# main.net
KiCad netlist of a schematic drawn in Altium Designer
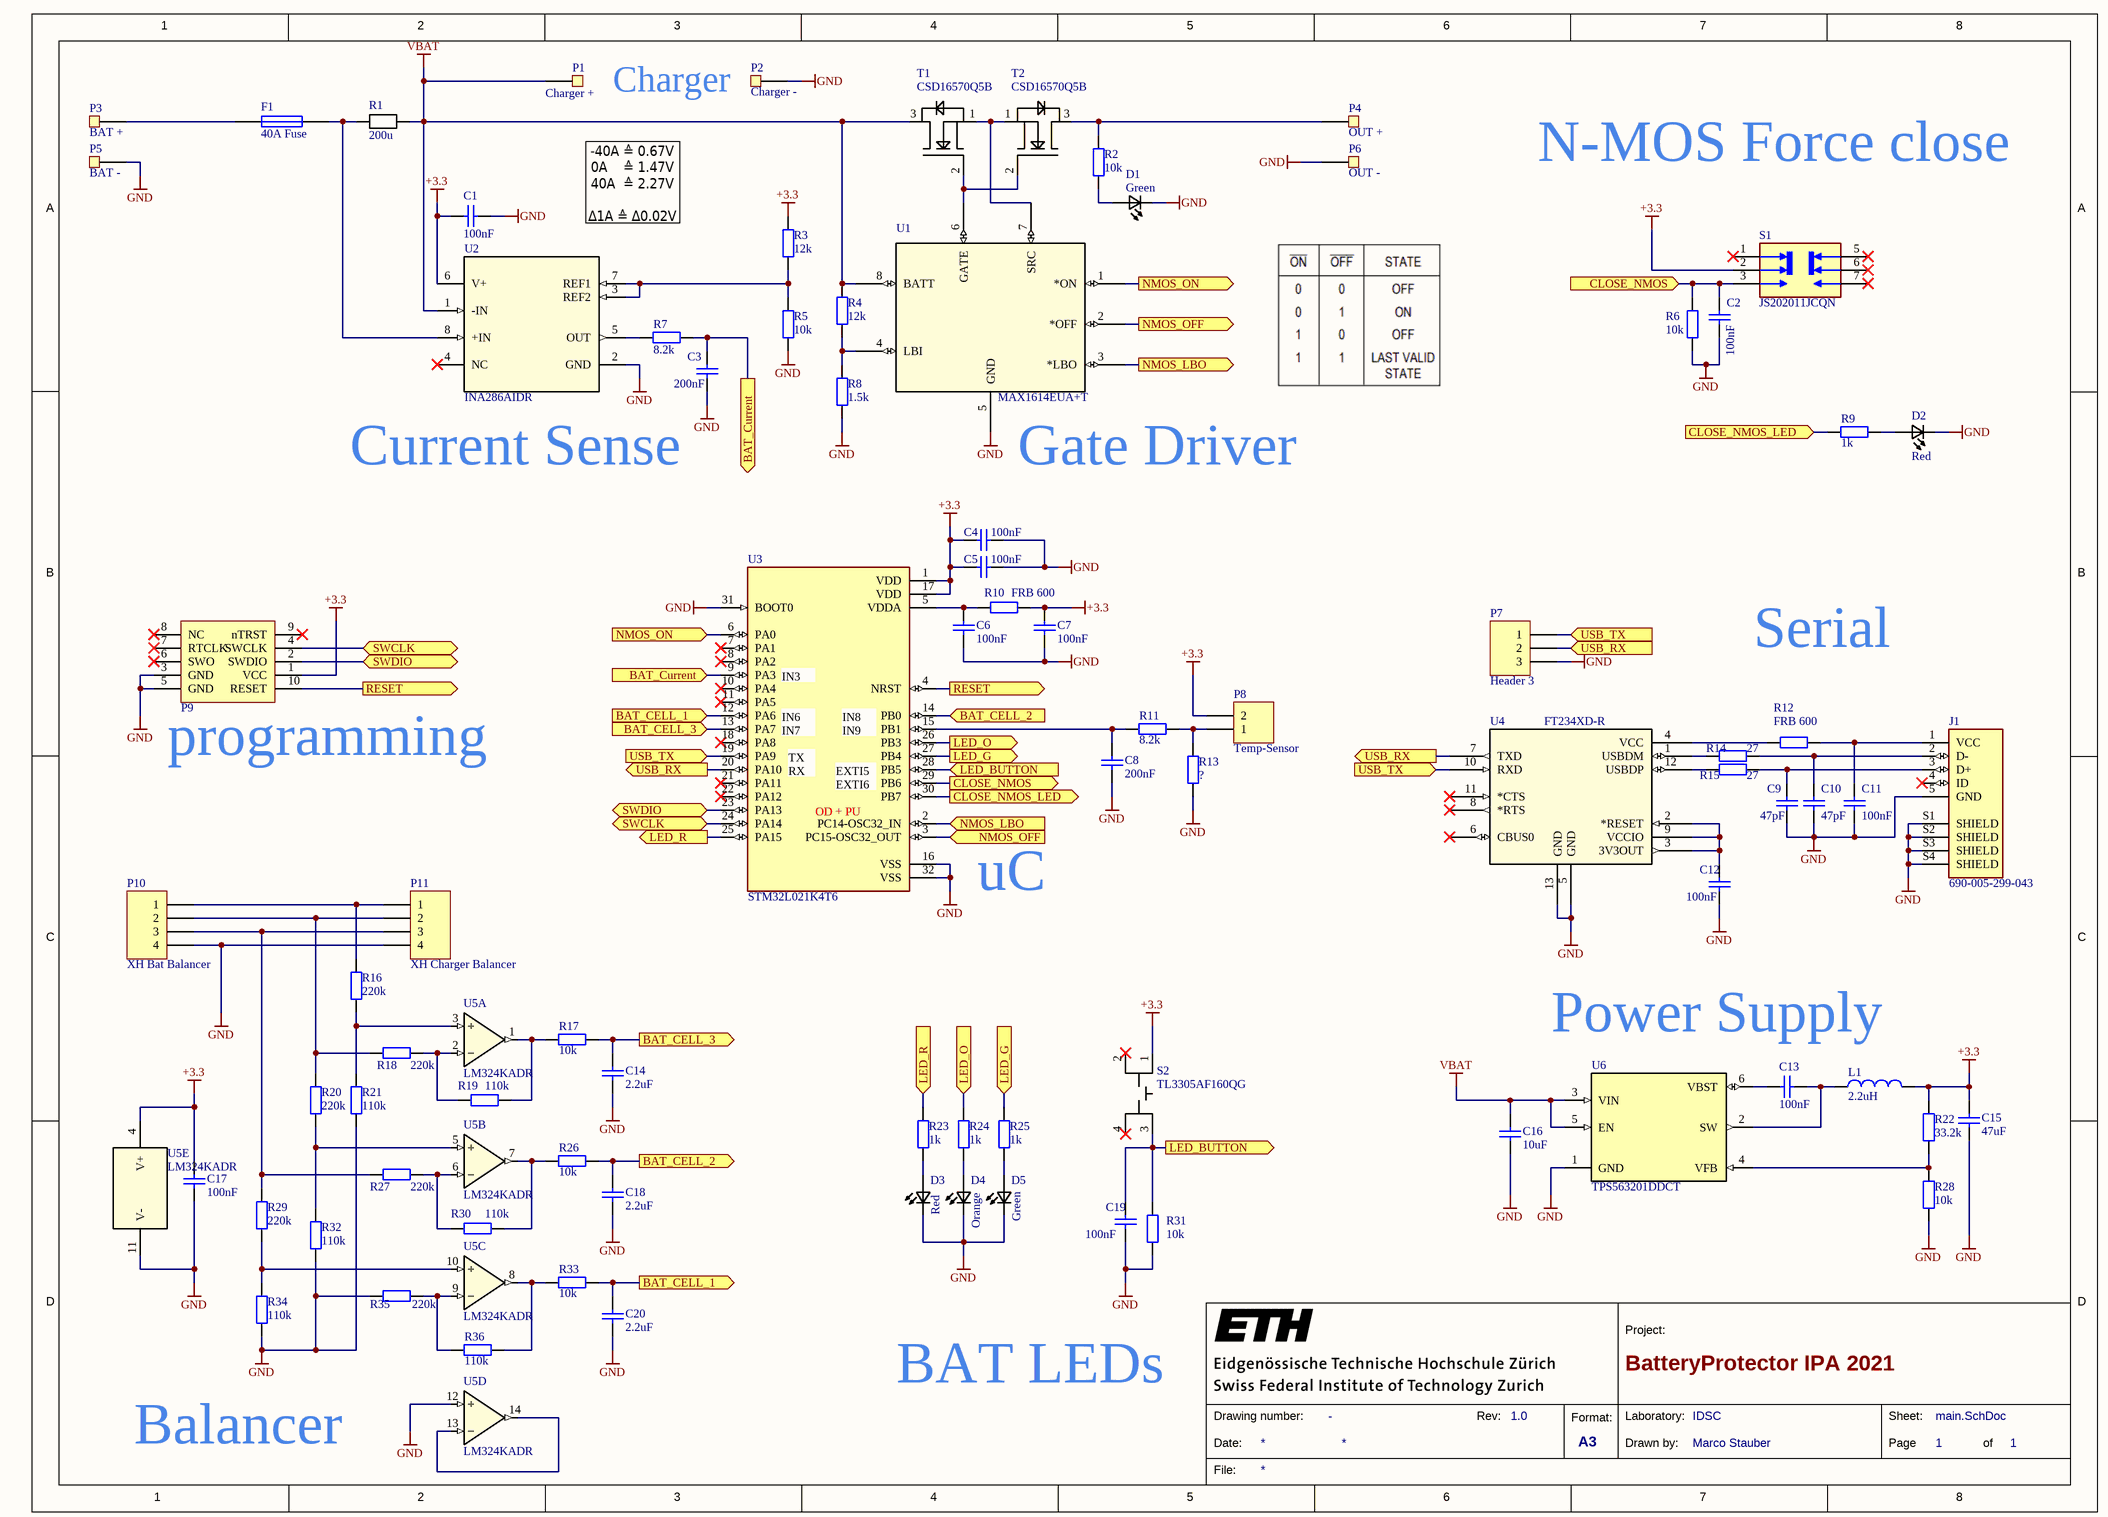
[diagram p0: main.SchDoc]

(export (version "E")
  (design (tool "Eeschema 10.0.6"))
  (components
    (comp (ref "C1")
      (value "100nF")
      (footprint "CAP_0402i_1005m -L")
      (description "capacitor")
      (libsource (lib "IDSC std generic parts") (part "Cap"))
    )
    (comp (ref "C2")
      (value "100nF")
      (footprint "CAP_0402i_1005m -L")
      (description "capacitor")
      (libsource (lib "IDSC std generic parts") (part "Cap"))
    )
    (comp (ref "C3")
      (value "200nF")
      (footprint "CAP_0402i_1005m -L")
      (description "capacitor")
      (libsource (lib "IDSC std generic parts") (part "Cap"))
    )
    (comp (ref "C4")
      (value "100nF")
      (footprint "CAP_0402i_1005m -L")
      (description "capacitor")
      (libsource (lib "IDSC std generic parts") (part "Cap"))
    )
    (comp (ref "C5")
      (value "100nF")
      (footprint "CAP_0402i_1005m -L")
      (description "capacitor")
      (libsource (lib "IDSC std generic parts") (part "Cap"))
    )
    (comp (ref "C6")
      (value "100nF")
      (footprint "CAP_0402i_1005m -L")
      (description "capacitor")
      (libsource (lib "IDSC std generic parts") (part "Cap"))
    )
    (comp (ref "C7")
      (value "100nF")
      (footprint "CAP_0402i_1005m -L")
      (description "capacitor")
      (libsource (lib "IDSC std generic parts") (part "Cap"))
    )
    (comp (ref "C8")
      (value "200nF")
      (footprint "CAP_0402i_1005m -L")
      (description "capacitor")
      (libsource (lib "IDSC std generic parts") (part "Cap"))
    )
    (comp (ref "C9")
      (value "47pF")
      (footprint "CAP_0402i_1005m -L")
      (description "capacitor")
      (libsource (lib "IDSC std generic parts") (part "Cap"))
    )
    (comp (ref "C10")
      (value "47pF")
      (footprint "CAP_0402i_1005m -L")
      (description "capacitor")
      (libsource (lib "IDSC std generic parts") (part "Cap"))
    )
    (comp (ref "C11")
      (value "100nF")
      (footprint "CAP_0402i_1005m -L")
      (description "capacitor")
      (libsource (lib "IDSC std generic parts") (part "Cap"))
    )
    (comp (ref "C12")
      (value "100nF")
      (footprint "CAP_0402i_1005m -L")
      (description "capacitor")
      (libsource (lib "IDSC std generic parts") (part "Cap"))
    )
    (comp (ref "C13")
      (value "100nF")
      (footprint "CAP_0402i_1005m -L")
      (description "capacitor")
      (libsource (lib "IDSC std generic parts") (part "Cap"))
    )
    (comp (ref "C14")
      (value "2.2uF")
      (footprint "CAP_0805i_2012m -L")
      (description "capacitor")
      (libsource (lib "IDSC std generic parts") (part "Cap"))
    )
    (comp (ref "C15")
      (value "47uF")
      (footprint "CAP_1206i_3216m -n")
      (description "capacitor")
      (libsource (lib "IDSC std generic parts") (part "Cap"))
    )
    (comp (ref "C16")
      (value "10uF")
      (footprint "CAP_0805i_2012m -L")
      (description "capacitor")
      (libsource (lib "IDSC std generic parts") (part "Cap"))
    )
    (comp (ref "C17")
      (value "100nF")
      (footprint "CAP_0402i_1005m -L")
      (description "capacitor")
      (libsource (lib "IDSC std generic parts") (part "Cap"))
    )
    (comp (ref "C18")
      (value "2.2uF")
      (footprint "CAP_0805i_2012m -L")
      (description "capacitor")
      (libsource (lib "IDSC std generic parts") (part "Cap"))
    )
    (comp (ref "C19")
      (value "100nF")
      (footprint "CAP_0402i_1005m -L")
      (description "capacitor")
      (libsource (lib "IDSC std generic parts") (part "Cap"))
    )
    (comp (ref "C20")
      (value "2.2uF")
      (footprint "CAP_0805i_2012m -L")
      (description "capacitor")
      (libsource (lib "IDSC std generic parts") (part "Cap"))
    )
    (comp (ref "D1")
      (value "Green")
      (footprint "0603_LED")
      (description "Red 631nm LED Indication - Discrete 2V 0603 _1608 Metric_")
      (fields (field (name "MF") "Lite-On Inc.") (field (name "DIGI-KEY_PART_NUMBER") "160-1447-1-ND"))
      (libsource (lib "BatteryProtector_LIB") (part "LTST-C191KRKT"))
    )
    (comp (ref "D2")
      (value "Red")
      (footprint "0603_LED")
      (description "Red 631nm LED Indication - Discrete 2V 0603 _1608 Metric_")
      (fields (field (name "MF") "Lite-On Inc.") (field (name "DIGI-KEY_PART_NUMBER") "160-1447-1-ND"))
      (libsource (lib "BatteryProtector_LIB") (part "LTST-C191KRKT"))
    )
    (comp (ref "D3")
      (value "Red")
      (footprint "0603_LED")
      (description "Red 631nm LED Indication - Discrete 2V 0603 _1608 Metric_")
      (fields (field (name "MF") "Lite-On Inc.") (field (name "DIGI-KEY_PART_NUMBER") "160-1447-1-ND"))
      (libsource (lib "BatteryProtector_LIB") (part "LTST-C191KRKT"))
    )
    (comp (ref "D4")
      (value "Orange")
      (footprint "0603_LED")
      (description "Red 631nm LED Indication - Discrete 2V 0603 _1608 Metric_")
      (fields (field (name "MF") "Lite-On Inc.") (field (name "DIGI-KEY_PART_NUMBER") "160-1447-1-ND"))
      (libsource (lib "BatteryProtector_LIB") (part "LTST-C191KRKT"))
    )
    (comp (ref "D5")
      (value "Green")
      (footprint "0603_LED")
      (description "Red 631nm LED Indication - Discrete 2V 0603 _1608 Metric_")
      (fields (field (name "MF") "Lite-On Inc.") (field (name "DIGI-KEY_PART_NUMBER") "160-1447-1-ND"))
      (libsource (lib "BatteryProtector_LIB") (part "LTST-C191KRKT"))
    )
    (comp (ref "F1")
      (value "40A Fuse")
      (footprint "FUSE_1206I_3216M_N")
      (description "Fuse")
      (libsource (lib "IDSC std generic parts") (part "Fuse"))
    )
    (comp (ref "J1")
      (value "690-005-299-043")
      (footprint "EDAC_690-005-299-043")
      (description "USB - mini B USB 2.0 Receptacle Connector 5 Position Surface Mount, Right Angle")
      (fields (field (name "MF") "EDAC Inc."))
      (libsource (lib "BatteryProtector_LIB") (part "690-005-299-043"))
    )
    (comp (ref "L1")
      (value "2.2uH")
      (footprint "IND_1210i_3225m -L")
      (description "Inductor")
      (libsource (lib "IDSC std generic parts") (part "Inductor"))
    )
    (comp (ref "P1")
      (value "Charger +")
      (footprint "AWG-10-Hole-1")
      (libsource (lib "BatteryProtector_LIB") (part "Pin"))
    )
    (comp (ref "P2") (value "Charger -") (footprint "AWG-10-Hole-1") (libsource (lib "") (part "Pin_2")))
    (comp (ref "P3") (value "BAT +") (footprint "AWG-10-Hole-1") (libsource (lib "") (part "Pin_1")))
    (comp (ref "P4")
      (value "OUT +")
      (footprint "AWG-10-Hole-1")
      (libsource (lib "BatteryProtector_LIB") (part "Pin"))
    )
    (comp (ref "P5") (value "BAT -") (footprint "AWG-10-Hole-1") (libsource (lib "") (part "Pin_1")))
    (comp (ref "P6")
      (value "OUT -")
      (footprint "AWG-10-Hole-1")
      (libsource (lib "BatteryProtector_LIB") (part "Pin"))
    )
    (comp (ref "P7")
      (value "Header 3")
      (footprint "1.27mm HDR1X3")
      (description "Header, 3-Pin")
      (libsource (lib "IDSC std connectors") (part "Header 3"))
    )
    (comp (ref "P8")
      (value "Temp-Sensor")
      (footprint "HDR1X2")
      (description "Header, 2-Pin")
      (libsource (lib "IDSC std connectors") (part "Header 2"))
    )
    (comp (ref "P9")
      (value "Tag-Connect TC2050-IDC-NL-No pin assigned")
      (footprint "TAG-CONNECT TC2050-IDC-NL 10-Pin")
      (description "10-pin pogo pin programing port")
      (libsource (lib "IDSC std connectors") (part "Tag-Connect TC2050-IDC-NL-No pin assigned"))
    )
    (comp (ref "P10")
      (value "XH Bat Balancer")
      (footprint "JST_B4B-XH-A(LF)(SN)")
      (description "Header, 4-Pin")
      (libsource (lib "BatteryProtector_LIB") (part "Header 4"))
    )
    (comp (ref "P11")
      (value "XH Charger Balancer")
      (footprint "JST_B4B-XH-A(LF)(SN)")
      (description "Header, 4-Pin")
      (libsource (lib "") (part "Header 4_1"))
    )
    (comp (ref "R1")
      (value "200u")
      (footprint "WSL3921L2000FEA")
      (description "RES 200 UOHM 1% 3W")
      (libsource (lib "BatteryProtector_LIB") (part "WSL3921L2000FEA"))
    )
    (comp (ref "R2")
      (value "10k")
      (footprint "RES_0402i_1005m -N")
      (description "Resistor")
      (libsource (lib "") (part "Res_2"))
    )
    (comp (ref "R3")
      (value "12k")
      (footprint "RES_0402i_1005m -N")
      (description "Resistor")
      (libsource (lib "") (part "Res_2"))
    )
    (comp (ref "R4")
      (value "12k")
      (footprint "RES_0402i_1005m -N")
      (description "Resistor")
      (libsource (lib "") (part "Res_2"))
    )
    (comp (ref "R5")
      (value "10k")
      (footprint "RES_0402i_1005m -N")
      (description "Resistor")
      (libsource (lib "") (part "Res_1"))
    )
    (comp (ref "R6")
      (value "10k")
      (footprint "RES_0402i_1005m -N")
      (description "Resistor")
      (libsource (lib "") (part "Res_1"))
    )
    (comp (ref "R7")
      (value "8.2k")
      (footprint "RES_0402m_1005i -L")
      (description "Resistor")
      (libsource (lib "IDSC std generic parts") (part "Res"))
    )
    (comp (ref "R8")
      (value "1.5k")
      (footprint "RES_0402i_1005m -N")
      (description "Resistor")
      (libsource (lib "") (part "Res_1"))
    )
    (comp (ref "R9")
      (value "1k")
      (footprint "RES_0402i_1005m -N")
      (description "Resistor")
      (libsource (lib "") (part "Res_3"))
    )
    (comp (ref "R10")
      (value "FRB 600")
      (footprint "RES_0603i_1608m -N")
      (description "Resistor")
      (libsource (lib "IDSC std generic parts") (part "Res"))
    )
    (comp (ref "R11")
      (value "8.2k")
      (footprint "RES_0402m_1005i -L")
      (description "Resistor")
      (libsource (lib "") (part "Res_2"))
    )
    (comp (ref "R12")
      (value "FRB 600")
      (footprint "RES_0603i_1608m -N")
      (description "Resistor")
      (libsource (lib "IDSC std generic parts") (part "Res"))
    )
    (comp (ref "R13")
      (value "?")
      (footprint "RES_0402m_1005i -L")
      (description "Resistor")
      (libsource (lib "IDSC std generic parts") (part "Res"))
    )
    (comp (ref "R14")
      (value "27")
      (footprint "RES_0402i_1005m -N")
      (description "Resistor")
      (libsource (lib "IDSC std generic parts") (part "Res"))
    )
    (comp (ref "R15")
      (value "27")
      (footprint "RES_0402i_1005m -N")
      (description "Resistor")
      (libsource (lib "IDSC std generic parts") (part "Res"))
    )
    (comp (ref "R16")
      (value "220k")
      (footprint "RES_0402i_1005m -N")
      (description "Resistor")
      (libsource (lib "") (part "Res_1"))
    )
    (comp (ref "R17")
      (value "10k")
      (footprint "RES_0402i_1005m -N")
      (description "Resistor")
      (libsource (lib "IDSC std generic parts") (part "Res"))
    )
    (comp (ref "R18")
      (value "220k")
      (footprint "RES_0402i_1005m -N")
      (description "Resistor")
      (libsource (lib "") (part "Res_3"))
    )
    (comp (ref "R19")
      (value "110k")
      (footprint "RES_0402i_1005m -N")
      (description "Resistor")
      (libsource (lib "") (part "Res_3"))
    )
    (comp (ref "R20")
      (value "220k")
      (footprint "RES_0402i_1005m -N")
      (description "Resistor")
      (libsource (lib "") (part "Res_1"))
    )
    (comp (ref "R21")
      (value "110k")
      (footprint "RES_0402i_1005m -N")
      (description "Resistor")
      (libsource (lib "") (part "Res_1"))
    )
    (comp (ref "R22")
      (value "33.2k")
      (footprint "RES_0402i_1005m -N")
      (description "Resistor")
      (libsource (lib "") (part "Res_1"))
    )
    (comp (ref "R23")
      (value "1k")
      (footprint "RES_0402i_1005m -N")
      (description "Resistor")
      (libsource (lib "") (part "Res_1"))
    )
    (comp (ref "R24")
      (value "1k")
      (footprint "RES_0402i_1005m -N")
      (description "Resistor")
      (libsource (lib "") (part "Res_1"))
    )
    (comp (ref "R25")
      (value "1k")
      (footprint "RES_0402i_1005m -N")
      (description "Resistor")
      (libsource (lib "") (part "Res_1"))
    )
    (comp (ref "R26")
      (value "10k")
      (footprint "RES_0402i_1005m -N")
      (description "Resistor")
      (libsource (lib "IDSC std generic parts") (part "Res"))
    )
    (comp (ref "R27")
      (value "220k")
      (footprint "RES_0402i_1005m -N")
      (description "Resistor")
      (libsource (lib "") (part "Res_3"))
    )
    (comp (ref "R28")
      (value "10k")
      (footprint "RES_0402i_1005m -N")
      (description "Resistor")
      (libsource (lib "") (part "Res_1"))
    )
    (comp (ref "R29")
      (value "220k")
      (footprint "RES_0402i_1005m -N")
      (description "Resistor")
      (libsource (lib "") (part "Res_1"))
    )
    (comp (ref "R30")
      (value "110k")
      (footprint "RES_0402i_1005m -N")
      (description "Resistor")
      (libsource (lib "") (part "Res_3"))
    )
    (comp (ref "R31")
      (value "10k")
      (footprint "RES_0402i_1005m -N")
      (description "Resistor")
      (libsource (lib "") (part "Res_1"))
    )
    (comp (ref "R32")
      (value "110k")
      (footprint "RES_0402i_1005m -N")
      (description "Resistor")
      (libsource (lib "") (part "Res_1"))
    )
    (comp (ref "R33")
      (value "10k")
      (footprint "RES_0402i_1005m -N")
      (description "Resistor")
      (libsource (lib "IDSC std generic parts") (part "Res"))
    )
    (comp (ref "R34")
      (value "110k")
      (footprint "RES_0402i_1005m -N")
      (description "Resistor")
      (libsource (lib "") (part "Res_1"))
    )
    (comp (ref "R35")
      (value "220k")
      (footprint "RES_0402i_1005m -N")
      (description "Resistor")
      (libsource (lib "") (part "Res_3"))
    )
    (comp (ref "R36")
      (value "110k")
      (footprint "RES_0402i_1005m -N")
      (description "Resistor")
      (libsource (lib "IDSC std generic parts") (part "Res"))
    )
    (comp (ref "S1")
      (value "JS202011JCQN")
      (footprint "SW_JS202011JCQN")
      (description "Slide Switch DPDT Surface Mount")
      (fields (field (name "MF") "C&K"))
      (libsource (lib "BatteryProtector_LIB") (part "JS202011JCQN"))
    )
    (comp (ref "S2")
      (value "TL3305AF160QG")
      (footprint "TL3305AF160QG")
      (libsource (lib "BatteryProtector_LIB") (part "TL3305AF160QG"))
    )
    (comp (ref "T1")
      (value "CSD16570Q5B")
      (footprint "CSD16570Q5B")
      (description "Power NMOS")
      (fields (field (name "COPYRIGHT") "Copyright (C) 2018 Accelerated Designs. All rights reserved"))
      (libsource (lib "BatteryProtector_LIB") (part "CSD16570Q5B"))
    )
    (comp (ref "T2")
      (value "CSD16570Q5B")
      (footprint "CSD16570Q5B")
      (description "Power NMOS")
      (fields (field (name "COPYRIGHT") "Copyright (C) 2018 Accelerated Designs. All rights reserved"))
      (libsource (lib "BatteryProtector_LIB") (part "CSD16570Q5B"))
    )
    (comp (ref "U1")
      (value "MAX1614EUA+T")
      (footprint "21-0036K_MXM-L")
      (description "No Description Available")
      (fields (field (name "COPYRIGHT") "Copyright (C) 2018 Accelerated Designs. All rights reserved"))
      (libsource (lib "BatteryProtector_LIB") (part "MAX1614EUA+T"))
    )
    (comp (ref "U2")
      (value "INA286AIDR")
      (footprint "D0008A_M")
      (description "No Description Available")
      (fields
        (field (name "ALTERNATE_PARTNUMBER") "INA286AID")
        (field (name "MANUFACTURER") "Texas Instruments")
        (field (name "COPYRIGHT") "Copyright (C) 2018 Accelerated Designs. All rights reserved")
      )
      (libsource (lib "BatteryProtector_LIB") (part "INA286AIDR"))
    )
    (comp (ref "U3")
      (value "STM32L021K4T6")
      (footprint "QFP80P900X900X160-32N")
      (description "ARM® Cortex®-M0+ STM32L0 Microcontroller IC 32-Bit 32MHz 32KB (32K x 8) FLASH 32-LQFP (7x7)")
      (fields (field (name "MP") "STM32L051K6T6") (field (name "MF") "STMicroelectronics"))
      (libsource (lib "BatteryProtector_LIB") (part "STM32L051K6T6"))
    )
    (comp (ref "U4")
      (value "FT234XD-R")
      (footprint "DFN-12_FTD")
      (description "No Description Available")
      (fields (field (name "COPYRIGHT") "Copyright (C) 2018 Accelerated Designs. All rights reserved"))
      (libsource (lib "BatteryProtector_LIB") (part "FT234XD-R"))
    )
    (comp (ref "U5")
      (value "LM324KADR")
      (footprint "SOIC127P600X175-14N")
      (fields (field (name "MP") "LMC6044IM/NOPB"))
      (libsource (lib "BatteryProtector_LIB") (part "LM324KADR"))
    )
    (comp (ref "U6")
      (value "TPS563201DDCT")
      (footprint "SOT95P280X110-6N")
      (fields (field (name "MP") "TPS561201DDCR") (field (name "MF") "Texas Instruments"))
      (libsource (lib "BatteryProtector_LIB") (part "TPS561201DDCR"))
    )
  )
  (nets
    (net (code "1") (name "+3.3") (class "Default")
      (node (ref "C1") (pin "2") (pinfunction "2_2") (pintype "passive"))
      (node (ref "C15") (pin "2") (pinfunction "2_2") (pintype "passive"))
      (node (ref "C17") (pin "2") (pinfunction "2_2") (pintype "passive"))
      (node (ref "C4") (pin "1") (pinfunction "1_1") (pintype "passive"))
      (node (ref "C5") (pin "1") (pinfunction "1_1") (pintype "passive"))
      (node (ref "C7") (pin "2") (pinfunction "2_2") (pintype "passive"))
      (node (ref "L1") (pin "2") (pinfunction "2_2") (pintype "passive"))
      (node (ref "P8") (pin "2") (pinfunction "2_2") (pintype "passive"))
      (node (ref "P9") (pin "1") (pinfunction "VCC_1") (pintype "passive"))
      (node (ref "R10") (pin "2") (pinfunction "2_2") (pintype "passive"))
      (node (ref "R22") (pin "2") (pinfunction "2_2") (pintype "passive"))
      (node (ref "R3") (pin "1") (pinfunction "1_1") (pintype "passive"))
      (node (ref "S1") (pin "2") (pinfunction "2_2") (pintype "passive"))
      (node (ref "S2") (pin "1") (pinfunction "1_1") (pintype "passive"))
      (node (ref "U2") (pin "6") (pinfunction "V+_6") (pintype "power_in"))
      (node (ref "U3") (pin "1") (pinfunction "VDD_1") (pintype "power_in"))
      (node (ref "U3") (pin "17") (pinfunction "VDD_17") (pintype "power_in"))
      (node (ref "U5") (pin "4") (pinfunction "V+_4") (pintype "power_in"))
    )
    (net (code "2") (name "/BAT_CELL_1") (class "Default")
      (node (ref "C20") (pin "2") (pinfunction "2_2") (pintype "passive"))
      (node (ref "R33") (pin "2") (pinfunction "2_2") (pintype "passive"))
      (node (ref "U3") (pin "12") (pinfunction "PA6_12") (pintype "bidirectional"))
    )
    (net (code "3") (name "/BAT_CELL_2") (class "Default")
      (node (ref "C18") (pin "2") (pinfunction "2_2") (pintype "passive"))
      (node (ref "R26") (pin "2") (pinfunction "2_2") (pintype "passive"))
      (node (ref "U3") (pin "14") (pinfunction "PB0_14") (pintype "bidirectional"))
    )
    (net (code "4") (name "/BAT_CELL_3") (class "Default")
      (node (ref "C14") (pin "2") (pinfunction "2_2") (pintype "passive"))
      (node (ref "R17") (pin "2") (pinfunction "2_2") (pintype "passive"))
      (node (ref "U3") (pin "13") (pinfunction "PA7_13") (pintype "bidirectional"))
    )
    (net (code "5") (name "/BAT_Current") (class "Default")
      (node (ref "C3") (pin "1") (pinfunction "1_1") (pintype "passive"))
      (node (ref "R7") (pin "2") (pinfunction "2_2") (pintype "passive"))
      (node (ref "U3") (pin "9") (pinfunction "PA3_9") (pintype "bidirectional"))
    )
    (net (code "6") (name "/CLOSE_NMOS") (class "Default")
      (node (ref "C2") (pin "2") (pinfunction "2_2") (pintype "passive"))
      (node (ref "R6") (pin "2") (pinfunction "2_2") (pintype "passive"))
      (node (ref "S1") (pin "3") (pinfunction "3_3") (pintype "passive"))
      (node (ref "U3") (pin "29") (pinfunction "PB6_29") (pintype "bidirectional"))
    )
    (net (code "7") (name "/CLOSE_NMOS_LED") (class "Default")
      (node (ref "R9") (pin "2") (pinfunction "2_2") (pintype "passive"))
      (node (ref "U3") (pin "30") (pinfunction "PB7_30") (pintype "bidirectional"))
    )
    (net (code "8") (name "/LED_BUTTON") (class "Default")
      (node (ref "C19") (pin "2") (pinfunction "2_2") (pintype "passive"))
      (node (ref "R31") (pin "2") (pinfunction "2_2") (pintype "passive"))
      (node (ref "S2") (pin "3") (pinfunction "3_3") (pintype "passive"))
      (node (ref "U3") (pin "28") (pinfunction "PB5_28") (pintype "bidirectional"))
    )
    (net (code "9") (name "/LED_G") (class "Default")
      (node (ref "R25") (pin "2") (pinfunction "2_2") (pintype "passive"))
      (node (ref "U3") (pin "27") (pinfunction "PB4_27") (pintype "bidirectional"))
    )
    (net (code "10") (name "/LED_O") (class "Default")
      (node (ref "R24") (pin "2") (pinfunction "2_2") (pintype "passive"))
      (node (ref "U3") (pin "26") (pinfunction "PB3_26") (pintype "bidirectional"))
    )
    (net (code "11") (name "/LED_R") (class "Default")
      (node (ref "R23") (pin "2") (pinfunction "2_2") (pintype "passive"))
      (node (ref "U3") (pin "25") (pinfunction "PA15_25") (pintype "bidirectional"))
    )
    (net (code "12") (name "/NMOS_LBO") (class "Default")
      (node (ref "U1") (pin "3") (pinfunction "*LBO_3") (pintype "bidirectional"))
      (node (ref "U3") (pin "2") (pinfunction "PC14-OSC32_IN_2") (pintype "bidirectional"))
    )
    (net (code "13") (name "/NMOS_OFF") (class "Default")
      (node (ref "U1") (pin "2") (pinfunction "*OFF_2") (pintype "bidirectional"))
      (node (ref "U3") (pin "3") (pinfunction "PC15-OSC32_OUT_3") (pintype "bidirectional"))
    )
    (net (code "14") (name "/NMOS_ON") (class "Default")
      (node (ref "U1") (pin "1") (pinfunction "*ON_1") (pintype "bidirectional"))
      (node (ref "U3") (pin "6") (pinfunction "PA0_6") (pintype "bidirectional"))
    )
    (net (code "15") (name "/RESET") (class "Default")
      (node (ref "P9") (pin "10") (pinfunction "RESET_10") (pintype "passive"))
      (node (ref "U3") (pin "4") (pinfunction "NRST_4") (pintype "bidirectional"))
    )
    (net (code "16") (name "/SWCLK") (class "Default")
      (node (ref "P9") (pin "4") (pinfunction "SWCLK_4") (pintype "passive"))
      (node (ref "U3") (pin "24") (pinfunction "PA14_24") (pintype "bidirectional"))
    )
    (net (code "17") (name "/SWDIO") (class "Default")
      (node (ref "P9") (pin "2") (pinfunction "SWDIO_2") (pintype "passive"))
      (node (ref "U3") (pin "23") (pinfunction "PA13_23") (pintype "bidirectional"))
    )
    (net (code "18") (name "/USB_RX") (class "Default")
      (node (ref "P7") (pin "2") (pinfunction "2_2") (pintype "passive"))
      (node (ref "U3") (pin "20") (pinfunction "PA10_20") (pintype "bidirectional"))
      (node (ref "U4") (pin "7") (pinfunction "TXD_7") (pintype "output"))
    )
    (net (code "19") (name "/USB_TX") (class "Default")
      (node (ref "P7") (pin "1") (pinfunction "1_1") (pintype "passive"))
      (node (ref "U3") (pin "19") (pinfunction "PA9_19") (pintype "bidirectional"))
      (node (ref "U4") (pin "10") (pinfunction "RXD_10") (pintype "input"))
    )
    (net (code "20") (name "GND") (class "Default")
      (node (ref "C1") (pin "1") (pinfunction "1_1") (pintype "passive"))
      (node (ref "C10") (pin "1") (pinfunction "1_1") (pintype "passive"))
      (node (ref "C11") (pin "1") (pinfunction "1_1") (pintype "passive"))
      (node (ref "C12") (pin "1") (pinfunction "1_1") (pintype "passive"))
      (node (ref "C14") (pin "1") (pinfunction "1_1") (pintype "passive"))
      (node (ref "C15") (pin "1") (pinfunction "1_1") (pintype "passive"))
      (node (ref "C16") (pin "1") (pinfunction "1_1") (pintype "passive"))
      (node (ref "C17") (pin "1") (pinfunction "1_1") (pintype "passive"))
      (node (ref "C18") (pin "1") (pinfunction "1_1") (pintype "passive"))
      (node (ref "C19") (pin "1") (pinfunction "1_1") (pintype "passive"))
      (node (ref "C2") (pin "1") (pinfunction "1_1") (pintype "passive"))
      (node (ref "C20") (pin "1") (pinfunction "1_1") (pintype "passive"))
      (node (ref "C3") (pin "2") (pinfunction "2_2") (pintype "passive"))
      (node (ref "C4") (pin "2") (pinfunction "2_2") (pintype "passive"))
      (node (ref "C5") (pin "2") (pinfunction "2_2") (pintype "passive"))
      (node (ref "C6") (pin "1") (pinfunction "1_1") (pintype "passive"))
      (node (ref "C7") (pin "1") (pinfunction "1_1") (pintype "passive"))
      (node (ref "C8") (pin "2") (pinfunction "2_2") (pintype "passive"))
      (node (ref "C9") (pin "1") (pinfunction "1_1") (pintype "passive"))
      (node (ref "D1") (pin "1") (pinfunction "K2_1") (pintype "passive"))
      (node (ref "D2") (pin "1") (pinfunction "K2_1") (pintype "passive"))
      (node (ref "D3") (pin "1") (pinfunction "K2_1") (pintype "passive"))
      (node (ref "D4") (pin "1") (pinfunction "K2_1") (pintype "passive"))
      (node (ref "D5") (pin "1") (pinfunction "K2_1") (pintype "passive"))
      (node (ref "J1") (pin "5") (pinfunction "GND_5") (pintype "power_in"))
      (node (ref "J1") (pin "S1") (pinfunction "SHIELD_S1") (pintype "passive"))
      (node (ref "J1") (pin "S2") (pinfunction "SHIELD_S2") (pintype "passive"))
      (node (ref "J1") (pin "S3") (pinfunction "SHIELD_S3") (pintype "passive"))
      (node (ref "J1") (pin "S4") (pinfunction "SHIELD_S4") (pintype "passive"))
      (node (ref "P10") (pin "4") (pinfunction "4_4") (pintype "passive"))
      (node (ref "P11") (pin "4") (pinfunction "4_4") (pintype "passive"))
      (node (ref "P2") (pin "1") (pinfunction "1_1") (pintype "passive"))
      (node (ref "P5") (pin "1") (pinfunction "1_1") (pintype "passive"))
      (node (ref "P6") (pin "1") (pinfunction "1_1") (pintype "passive"))
      (node (ref "P7") (pin "3") (pinfunction "3_3") (pintype "passive"))
      (node (ref "P9") (pin "3") (pinfunction "GND_3") (pintype "passive"))
      (node (ref "P9") (pin "5") (pinfunction "GND_5") (pintype "passive"))
      (node (ref "R13") (pin "1") (pinfunction "1_1") (pintype "passive"))
      (node (ref "R21") (pin "1") (pinfunction "1_1") (pintype "passive"))
      (node (ref "R28") (pin "1") (pinfunction "1_1") (pintype "passive"))
      (node (ref "R31") (pin "1") (pinfunction "1_1") (pintype "passive"))
      (node (ref "R32") (pin "1") (pinfunction "1_1") (pintype "passive"))
      (node (ref "R34") (pin "1") (pinfunction "1_1") (pintype "passive"))
      (node (ref "R35") (pin "2") (pinfunction "2_2") (pintype "passive"))
      (node (ref "R5") (pin "1") (pinfunction "1_1") (pintype "passive"))
      (node (ref "R6") (pin "1") (pinfunction "1_1") (pintype "passive"))
      (node (ref "R8") (pin "1") (pinfunction "1_1") (pintype "passive"))
      (node (ref "U1") (pin "5") (pinfunction "GND_5") (pintype "power_in"))
      (node (ref "U2") (pin "2") (pinfunction "GND_2") (pintype "power_in"))
      (node (ref "U3") (pin "16") (pinfunction "VSS_16") (pintype "power_in"))
      (node (ref "U3") (pin "31") (pinfunction "BOOT0_31") (pintype "input"))
      (node (ref "U3") (pin "32") (pinfunction "VSS_32") (pintype "power_in"))
      (node (ref "U4") (pin "13") (pinfunction "GND_13") (pintype "power_in"))
      (node (ref "U4") (pin "5") (pinfunction "GND_5") (pintype "power_in"))
      (node (ref "U5") (pin "11") (pinfunction "V-_11") (pintype "power_in"))
      (node (ref "U5") (pin "12") (pinfunction "INPUTSA_12") (pintype "input"))
      (node (ref "U6") (pin "1") (pinfunction "GND_1") (pintype "power_in"))
    )
    (net (code "21") (name "Net-(D1-A2)") (class "Default")
      (node (ref "D1") (pin "2") (pinfunction "A2_2") (pintype "passive"))
      (node (ref "R2") (pin "2") (pinfunction "2_2") (pintype "passive"))
    )
    (net (code "22") (name "Net-(D2-A2)") (class "Default")
      (node (ref "D2") (pin "2") (pinfunction "A2_2") (pintype "passive"))
      (node (ref "R9") (pin "1") (pinfunction "1_1") (pintype "passive"))
    )
    (net (code "23") (name "Net-(D3-A2)") (class "Default")
      (node (ref "D3") (pin "2") (pinfunction "A2_2") (pintype "passive"))
      (node (ref "R23") (pin "1") (pinfunction "1_1") (pintype "passive"))
    )
    (net (code "24") (name "Net-(D4-A2)") (class "Default")
      (node (ref "D4") (pin "2") (pinfunction "A2_2") (pintype "passive"))
      (node (ref "R24") (pin "1") (pinfunction "1_1") (pintype "passive"))
    )
    (net (code "25") (name "Net-(D5-A2)") (class "Default")
      (node (ref "D5") (pin "2") (pinfunction "A2_2") (pintype "passive"))
      (node (ref "R25") (pin "1") (pinfunction "1_1") (pintype "passive"))
    )
    (net (code "26") (name "Net-(F1-Pad1)") (class "Default")
      (node (ref "F1") (pin "1") (pinfunction "1_1") (pintype "passive"))
      (node (ref "P3") (pin "1") (pinfunction "1_1") (pintype "passive"))
    )
    (net (code "27") (name "Net-(J1-D+)") (class "Default")
      (node (ref "C9") (pin "2") (pinfunction "2_2") (pintype "passive"))
      (node (ref "J1") (pin "3") (pinfunction "D+_3") (pintype "bidirectional"))
      (node (ref "R15") (pin "2") (pinfunction "2_2") (pintype "passive"))
    )
    (net (code "28") (name "Net-(J1-D-)") (class "Default")
      (node (ref "C10") (pin "2") (pinfunction "2_2") (pintype "passive"))
      (node (ref "J1") (pin "2") (pinfunction "D-_2") (pintype "bidirectional"))
      (node (ref "R14") (pin "2") (pinfunction "2_2") (pintype "passive"))
    )
    (net (code "29") (name "Net-(J1-VCC)") (class "Default")
      (node (ref "C11") (pin "2") (pinfunction "2_2") (pintype "passive"))
      (node (ref "J1") (pin "1") (pinfunction "VCC_1") (pintype "power_in"))
      (node (ref "R12") (pin "2") (pinfunction "2_2") (pintype "passive"))
    )
    (net (code "30") (name "Net-(P8-Pad1)") (class "Default")
      (node (ref "P8") (pin "1") (pinfunction "1_1") (pintype "passive"))
      (node (ref "R11") (pin "1") (pinfunction "1_1") (pintype "passive"))
      (node (ref "R13") (pin "2") (pinfunction "2_2") (pintype "passive"))
    )
    (net (code "31") (name "Net-(P10-Pad1)") (class "Default")
      (node (ref "P10") (pin "1") (pinfunction "1_1") (pintype "passive"))
      (node (ref "P11") (pin "1") (pinfunction "1_1") (pintype "passive"))
      (node (ref "R16") (pin "2") (pinfunction "2_2") (pintype "passive"))
    )
    (net (code "32") (name "Net-(P10-Pad2)") (class "Default")
      (node (ref "P10") (pin "2") (pinfunction "2_2") (pintype "passive"))
      (node (ref "P11") (pin "2") (pinfunction "2_2") (pintype "passive"))
      (node (ref "R18") (pin "2") (pinfunction "2_2") (pintype "passive"))
      (node (ref "R20") (pin "2") (pinfunction "2_2") (pintype "passive"))
    )
    (net (code "33") (name "Net-(P10-Pad3)") (class "Default")
      (node (ref "P10") (pin "3") (pinfunction "3_3") (pintype "passive"))
      (node (ref "P11") (pin "3") (pinfunction "3_3") (pintype "passive"))
      (node (ref "R27") (pin "2") (pinfunction "2_2") (pintype "passive"))
      (node (ref "R29") (pin "2") (pinfunction "2_2") (pintype "passive"))
    )
    (net (code "34") (name "Net-(R16-Pad1)") (class "Default")
      (node (ref "R16") (pin "1") (pinfunction "1_1") (pintype "passive"))
      (node (ref "R21") (pin "2") (pinfunction "2_2") (pintype "passive"))
      (node (ref "U5") (pin "3") (pinfunction "INPUTSA_3") (pintype "input"))
    )
    (net (code "35") (name "Net-(R18-Pad1)") (class "Default")
      (node (ref "R18") (pin "1") (pinfunction "1_1") (pintype "passive"))
      (node (ref "R19") (pin "2") (pinfunction "2_2") (pintype "passive"))
      (node (ref "U5") (pin "2") (pinfunction "INPUTSA_2") (pintype "input"))
    )
    (net (code "36") (name "Net-(R20-Pad1)") (class "Default")
      (node (ref "R20") (pin "1") (pinfunction "1_1") (pintype "passive"))
      (node (ref "R32") (pin "2") (pinfunction "2_2") (pintype "passive"))
      (node (ref "U5") (pin "5") (pinfunction "INPUTSA_5") (pintype "input"))
    )
    (net (code "37") (name "Net-(R27-Pad1)") (class "Default")
      (node (ref "R27") (pin "1") (pinfunction "1_1") (pintype "passive"))
      (node (ref "R30") (pin "2") (pinfunction "2_2") (pintype "passive"))
      (node (ref "U5") (pin "6") (pinfunction "INPUTSA_6") (pintype "input"))
    )
    (net (code "38") (name "Net-(R29-Pad1)") (class "Default")
      (node (ref "R29") (pin "1") (pinfunction "1_1") (pintype "passive"))
      (node (ref "R34") (pin "2") (pinfunction "2_2") (pintype "passive"))
      (node (ref "U5") (pin "10") (pinfunction "INPUTSA_10") (pintype "input"))
    )
    (net (code "39") (name "Net-(R35-Pad1)") (class "Default")
      (node (ref "R35") (pin "1") (pinfunction "1_1") (pintype "passive"))
      (node (ref "R36") (pin "1") (pinfunction "1_1") (pintype "passive"))
      (node (ref "U5") (pin "9") (pinfunction "INPUTSA_9") (pintype "input"))
    )
    (net (code "40") (name "Net-(T1-G)") (class "Default")
      (node (ref "T1") (pin "2") (pinfunction "G_2") (pintype "passive"))
      (node (ref "T2") (pin "2") (pinfunction "G_2") (pintype "passive"))
      (node (ref "U1") (pin "6") (pinfunction "GATE_6") (pintype "bidirectional"))
    )
    (net (code "41") (name "Net-(T1-S)") (class "Default")
      (node (ref "T1") (pin "1") (pinfunction "S_1") (pintype "passive"))
      (node (ref "T2") (pin "1") (pinfunction "S_1") (pintype "passive"))
      (node (ref "U1") (pin "7") (pinfunction "SRC_7") (pintype "bidirectional"))
    )
    (net (code "42") (name "Net-(T2-D)") (class "Default")
      (node (ref "P4") (pin "1") (pinfunction "1_1") (pintype "passive"))
      (node (ref "R2") (pin "1") (pinfunction "1_1") (pintype "passive"))
      (node (ref "T2") (pin "3") (pinfunction "D_3") (pintype "passive"))
    )
    (net (code "43") (name "Net-(U1-LBI)") (class "Default")
      (node (ref "R4") (pin "2") (pinfunction "2_2") (pintype "passive"))
      (node (ref "R8") (pin "2") (pinfunction "2_2") (pintype "passive"))
      (node (ref "U1") (pin "4") (pinfunction "LBI_4") (pintype "bidirectional"))
    )
    (net (code "44") (name "Net-(U2-+IN)") (class "Default")
      (node (ref "F1") (pin "2") (pinfunction "2_2") (pintype "passive"))
      (node (ref "R1") (pin "1") (pinfunction "1_1") (pintype "passive"))
      (node (ref "U2") (pin "8") (pinfunction "+IN_8") (pintype "input"))
    )
    (net (code "45") (name "Net-(U2-OUT)") (class "Default")
      (node (ref "R7") (pin "1") (pinfunction "1_1") (pintype "passive"))
      (node (ref "U2") (pin "5") (pinfunction "OUT_5") (pintype "output"))
    )
    (net (code "46") (name "Net-(U2-REF1)") (class "Default")
      (node (ref "R3") (pin "2") (pinfunction "2_2") (pintype "passive"))
      (node (ref "R5") (pin "2") (pinfunction "2_2") (pintype "passive"))
      (node (ref "U2") (pin "3") (pinfunction "REF2_3") (pintype "input"))
      (node (ref "U2") (pin "7") (pinfunction "REF1_7") (pintype "input"))
    )
    (net (code "47") (name "Net-(U3-PB1)") (class "Default")
      (node (ref "C8") (pin "1") (pinfunction "1_1") (pintype "passive"))
      (node (ref "R11") (pin "2") (pinfunction "2_2") (pintype "passive"))
      (node (ref "U3") (pin "15") (pinfunction "PB1_15") (pintype "bidirectional"))
    )
    (net (code "48") (name "Net-(U3-VDDA)") (class "Default")
      (node (ref "C6") (pin "2") (pinfunction "2_2") (pintype "passive"))
      (node (ref "R10") (pin "1") (pinfunction "1_1") (pintype "passive"))
      (node (ref "U3") (pin "5") (pinfunction "VDDA_5") (pintype "power_in"))
    )
    (net (code "49") (name "Net-(U4-*RESET)") (class "Default")
      (node (ref "C12") (pin "2") (pinfunction "2_2") (pintype "passive"))
      (node (ref "U4") (pin "2") (pinfunction "*RESET_2") (pintype "input"))
      (node (ref "U4") (pin "3") (pinfunction "3V3OUT_3") (pintype "output"))
      (node (ref "U4") (pin "9") (pinfunction "VCCIO_9") (pintype "power_in"))
    )
    (net (code "50") (name "Net-(U4-USBDM)") (class "Default")
      (node (ref "R14") (pin "1") (pinfunction "1_1") (pintype "passive"))
      (node (ref "U4") (pin "1") (pinfunction "USBDM_1") (pintype "bidirectional"))
    )
    (net (code "51") (name "Net-(U4-USBDP)") (class "Default")
      (node (ref "R15") (pin "1") (pinfunction "1_1") (pintype "passive"))
      (node (ref "U4") (pin "12") (pinfunction "USBDP_12") (pintype "bidirectional"))
    )
    (net (code "52") (name "Net-(U4-VCC)") (class "Default")
      (node (ref "R12") (pin "1") (pinfunction "1_1") (pintype "passive"))
      (node (ref "U4") (pin "4") (pinfunction "VCC_4") (pintype "power_in"))
    )
    (net (code "53") (name "Net-(U5A-OUTPUTA)") (class "Default")
      (node (ref "R17") (pin "1") (pinfunction "1_1") (pintype "passive"))
      (node (ref "R19") (pin "1") (pinfunction "1_1") (pintype "passive"))
      (node (ref "U5") (pin "1") (pinfunction "OUTPUTA_1") (pintype "output"))
    )
    (net (code "54") (name "Net-(U5B-OUTPUTA)") (class "Default")
      (node (ref "R26") (pin "1") (pinfunction "1_1") (pintype "passive"))
      (node (ref "R30") (pin "1") (pinfunction "1_1") (pintype "passive"))
      (node (ref "U5") (pin "7") (pinfunction "OUTPUTA_7") (pintype "output"))
    )
    (net (code "55") (name "Net-(U5C-OUTPUTA)") (class "Default")
      (node (ref "R33") (pin "1") (pinfunction "1_1") (pintype "passive"))
      (node (ref "R36") (pin "2") (pinfunction "2_2") (pintype "passive"))
      (node (ref "U5") (pin "8") (pinfunction "OUTPUTA_8") (pintype "output"))
    )
    (net (code "56") (name "Net-(U5D-OUTPUTA)") (class "Default")
      (node (ref "U5") (pin "13") (pinfunction "INPUTSA_13") (pintype "input"))
      (node (ref "U5") (pin "14") (pinfunction "OUTPUTA_14") (pintype "output"))
    )
    (net (code "57") (name "Net-(U6-SW)") (class "Default")
      (node (ref "C13") (pin "2") (pinfunction "2_2") (pintype "passive"))
      (node (ref "L1") (pin "1") (pinfunction "1_1") (pintype "passive"))
      (node (ref "U6") (pin "2") (pinfunction "SW_2") (pintype "output"))
    )
    (net (code "58") (name "Net-(U6-VBST)") (class "Default")
      (node (ref "C13") (pin "1") (pinfunction "1_1") (pintype "passive"))
      (node (ref "U6") (pin "6") (pinfunction "VBST_6") (pintype "bidirectional"))
    )
    (net (code "59") (name "Net-(U6-VFB)") (class "Default")
      (node (ref "R22") (pin "1") (pinfunction "1_1") (pintype "passive"))
      (node (ref "R28") (pin "2") (pinfunction "2_2") (pintype "passive"))
      (node (ref "U6") (pin "4") (pinfunction "VFB_4") (pintype "input"))
    )
    (net (code "60") (name "VBAT") (class "Default")
      (node (ref "C16") (pin "2") (pinfunction "2_2") (pintype "passive"))
      (node (ref "P1") (pin "1") (pinfunction "1_1") (pintype "passive"))
      (node (ref "R1") (pin "2") (pinfunction "2_2") (pintype "passive"))
      (node (ref "R4") (pin "1") (pinfunction "1_1") (pintype "passive"))
      (node (ref "T1") (pin "3") (pinfunction "D_3") (pintype "passive"))
      (node (ref "U1") (pin "8") (pinfunction "BATT_8") (pintype "bidirectional"))
      (node (ref "U2") (pin "1") (pinfunction "-IN_1") (pintype "input"))
      (node (ref "U6") (pin "3") (pinfunction "VIN_3") (pintype "input"))
      (node (ref "U6") (pin "5") (pinfunction "EN_5") (pintype "input"))
    )
    (net (code "61") (name "unconnected-(J1-ID-Pad4)") (class "Default")
      (node (ref "J1") (pin "4") (pinfunction "ID_4") (pintype "bidirectional+no_connect"))
    )
    (net (code "62") (name "unconnected-(P9-NC-Pad8)") (class "Default")
      (node (ref "P9") (pin "8") (pinfunction "NC_8") (pintype "passive+no_connect"))
    )
    (net (code "63") (name "unconnected-(P9-RTCLK-Pad7)") (class "Default")
      (node (ref "P9") (pin "7") (pinfunction "RTCLK_7") (pintype "passive+no_connect"))
    )
    (net (code "64") (name "unconnected-(P9-SWO-Pad6)") (class "Default")
      (node (ref "P9") (pin "6") (pinfunction "SWO_6") (pintype "passive+no_connect"))
    )
    (net (code "65") (name "unconnected-(P9-nTRST-Pad9)") (class "Default")
      (node (ref "P9") (pin "9") (pinfunction "nTRST_9") (pintype "passive+no_connect"))
    )
    (net (code "66") (name "unconnected-(S1-Pad1)") (class "Default")
      (node (ref "S1") (pin "1") (pinfunction "1_1") (pintype "passive+no_connect"))
    )
    (net (code "67") (name "unconnected-(S1-Pad5)") (class "Default")
      (node (ref "S1") (pin "5") (pinfunction "5_5") (pintype "passive+no_connect"))
    )
    (net (code "68") (name "unconnected-(S1-Pad6)") (class "Default")
      (node (ref "S1") (pin "6") (pinfunction "6_6") (pintype "passive+no_connect"))
    )
    (net (code "69") (name "unconnected-(S1-Pad7)") (class "Default")
      (node (ref "S1") (pin "7") (pinfunction "7_7") (pintype "passive+no_connect"))
    )
    (net (code "70") (name "unconnected-(S2-Pad2)") (class "Default")
      (node (ref "S2") (pin "2") (pinfunction "2_2") (pintype "passive+no_connect"))
    )
    (net (code "71") (name "unconnected-(S2-Pad4)") (class "Default")
      (node (ref "S2") (pin "4") (pinfunction "4_4") (pintype "passive+no_connect"))
    )
    (net (code "72") (name "unconnected-(U2-NC-Pad4)") (class "Default")
      (node (ref "U2") (pin "4") (pinfunction "NC_4") (pintype "passive+no_connect"))
    )
    (net (code "73") (name "unconnected-(U3-PA1-Pad7)") (class "Default")
      (node (ref "U3") (pin "7") (pinfunction "PA1_7") (pintype "bidirectional+no_connect"))
    )
    (net (code "74") (name "unconnected-(U3-PA2-Pad8)") (class "Default")
      (node (ref "U3") (pin "8") (pinfunction "PA2_8") (pintype "bidirectional+no_connect"))
    )
    (net (code "75") (name "unconnected-(U3-PA4-Pad10)") (class "Default")
      (node (ref "U3") (pin "10") (pinfunction "PA4_10") (pintype "bidirectional+no_connect"))
    )
    (net (code "76") (name "unconnected-(U3-PA5-Pad11)") (class "Default")
      (node (ref "U3") (pin "11") (pinfunction "PA5_11") (pintype "bidirectional+no_connect"))
    )
    (net (code "77") (name "unconnected-(U3-PA8-Pad18)") (class "Default")
      (node (ref "U3") (pin "18") (pinfunction "PA8_18") (pintype "bidirectional+no_connect"))
    )
    (net (code "78") (name "unconnected-(U3-PA11-Pad21)") (class "Default")
      (node (ref "U3") (pin "21") (pinfunction "PA11_21") (pintype "bidirectional+no_connect"))
    )
    (net (code "79") (name "unconnected-(U3-PA12-Pad22)") (class "Default")
      (node (ref "U3") (pin "22") (pinfunction "PA12_22") (pintype "bidirectional+no_connect"))
    )
    (net (code "80") (name "unconnected-(U4-*CTS-Pad11)") (class "Default")
      (node (ref "U4") (pin "11") (pinfunction "*CTS_11") (pintype "input+no_connect"))
    )
    (net (code "81") (name "unconnected-(U4-*RTS-Pad8)") (class "Default")
      (node (ref "U4") (pin "8") (pinfunction "*RTS_8") (pintype "output+no_connect"))
    )
    (net (code "82") (name "unconnected-(U4-CBUS0-Pad6)") (class "Default")
      (node (ref "U4") (pin "6") (pinfunction "CBUS0_6") (pintype "bidirectional+no_connect"))
    )
  )
)
